# LCL_pin_bias.net
KiCad netlist of a schematic drawn in Altium Designer
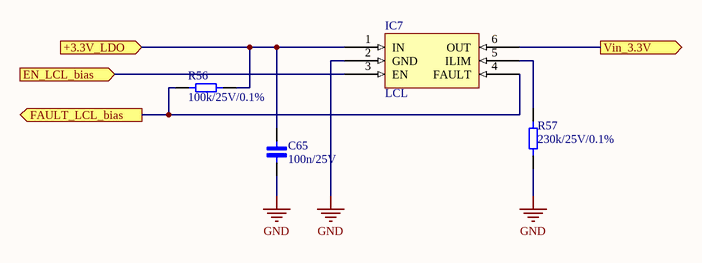
[diagram p0: LCL_pin_bias.SchDoc]

(export (version "E")
  (design (tool "Eeschema 10.0.6"))
  (components
    (comp (ref "C65")
      (value "100n/25V")
      (footprint "Cap_0402")
      (description "Ceramic Capacitor 100n / 0402 / 25V / ±5%, Wurth Elektronik MLCC")
      (libsource (lib "Cubesat_lib") (part "Cap_0402_100n"))
    )
    (comp (ref "IC7")
      (value "LCL")
      (footprint "SOT-23-6")
      (description "Latch-off Current Limiter")
      (libsource (lib "Cubesat_lib") (part "TPS2553"))
    )
    (comp (ref "R56")
      (value "100k/25V/0.1%")
      (footprint "RES_0402")
      (description "Vishay, thin film resistor 100k/25V/0.1%")
      (libsource (lib "Cubesat_lib") (part "Res_0402_100k"))
    )
    (comp (ref "R57")
      (value "230k/25V/0.1%")
      (footprint "RES_0402")
      (description "Vishay, thin film resistor 230k/25V/0.1%")
      (libsource (lib "Cubesat_lib") (part "Res_0402_230k"))
    )
  )
  (nets
    (net (code "1") (name "/+3.3V_LDO") (class "Default")
      (node (ref "C65") (pin "2") (pinfunction "2_2") (pintype "passive"))
      (node (ref "IC7") (pin "1") (pinfunction "IN_1") (pintype "input"))
      (node (ref "R56") (pin "1") (pinfunction "1_1") (pintype "passive"))
    )
    (net (code "2") (name "/EN_LCL_bias") (class "Default")
      (node (ref "IC7") (pin "3") (pinfunction "EN_3") (pintype "input"))
    )
    (net (code "3") (name "/FAULT_LCL_bias") (class "Default")
      (node (ref "IC7") (pin "4") (pinfunction "FAULT_4") (pintype "input"))
      (node (ref "R56") (pin "2") (pinfunction "2_2") (pintype "passive"))
    )
    (net (code "4") (name "/Vin_3.3V") (class "Default")
      (node (ref "IC7") (pin "6") (pinfunction "OUT_6") (pintype "input"))
    )
    (net (code "5") (name "GND") (class "Default")
      (node (ref "C65") (pin "1") (pinfunction "1_1") (pintype "passive"))
      (node (ref "IC7") (pin "2") (pinfunction "GND_2") (pintype "input"))
      (node (ref "R57") (pin "1") (pinfunction "1_1") (pintype "passive"))
    )
    (net (code "6") (name "Net-(IC7-ILIM)") (class "Default")
      (node (ref "IC7") (pin "5") (pinfunction "ILIM_5") (pintype "input"))
      (node (ref "R57") (pin "2") (pinfunction "2_2") (pintype "passive"))
    )
  )
)
